# xbee_2017.net
KiCad netlist of a schematic drawn in EAGLE
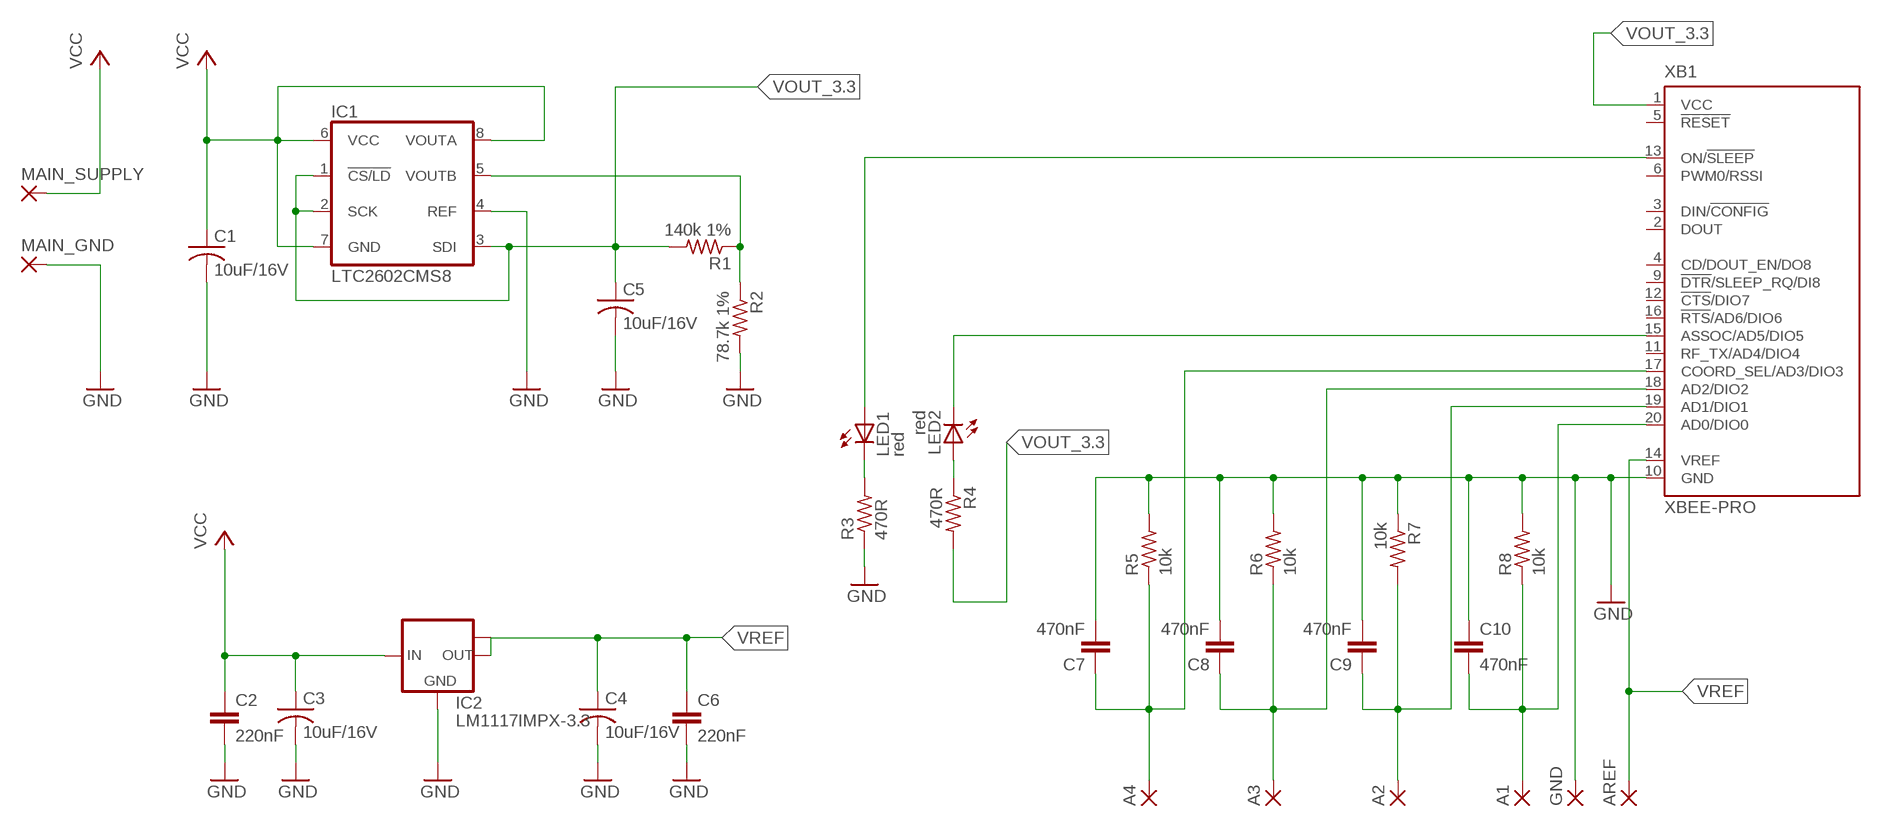
[diagram p0: schematic, sheet 1]

(export (version "E")
  (design (tool "Eeschema 10.0.6"))
  (components
    (comp (ref "A1")
      (value "2,54/0,9")
      (footprint "eagle-import:2,54_0,9")
      (libsource (lib "eagle-import") (part "2,54/0,9"))
    )
    (comp (ref "A2")
      (value "2,54/0,9")
      (footprint "eagle-import:2,54_0,9")
      (libsource (lib "eagle-import") (part "2,54/0,9"))
    )
    (comp (ref "A3")
      (value "2,54/0,9")
      (footprint "eagle-import:2,54_0,9")
      (libsource (lib "eagle-import") (part "2,54/0,9"))
    )
    (comp (ref "A4")
      (value "2,54/0,9")
      (footprint "eagle-import:2,54_0,9")
      (libsource (lib "eagle-import") (part "2,54/0,9"))
    )
    (comp (ref "AREF")
      (value "2,54/0,9")
      (footprint "eagle-import:2,54_0,9")
      (libsource (lib "eagle-import") (part "2,54/0,9"))
    )
    (comp (ref "C1")
      (value "10uF/16V")
      (footprint "eagle-import:C025-030X050")
      (libsource (lib "eagle-import") (part "C-US025-030X050"))
    )
    (comp (ref "C2")
      (value "220nF")
      (footprint "eagle-import:C025-025X050")
      (libsource (lib "eagle-import") (part "C-EU025-025X050"))
    )
    (comp (ref "C3")
      (value "10uF/16V")
      (footprint "eagle-import:C025-030X050")
      (libsource (lib "eagle-import") (part "C-US025-030X050"))
    )
    (comp (ref "C4")
      (value "10uF/16V")
      (footprint "eagle-import:C025-030X050")
      (libsource (lib "eagle-import") (part "C-US025-030X050"))
    )
    (comp (ref "C5")
      (value "10uF/16V")
      (footprint "eagle-import:C025-030X050")
      (libsource (lib "eagle-import") (part "C-US025-030X050"))
    )
    (comp (ref "C6")
      (value "220nF")
      (footprint "eagle-import:C025-025X050")
      (libsource (lib "eagle-import") (part "C-EU025-025X050"))
    )
    (comp (ref "C7")
      (value "470nF")
      (footprint "eagle-import:C5B2.5")
      (libsource (lib "eagle-import") (part "C5/2.5"))
    )
    (comp (ref "C8")
      (value "470nF")
      (footprint "eagle-import:C5B2.5")
      (libsource (lib "eagle-import") (part "C5/2.5"))
    )
    (comp (ref "C9")
      (value "470nF")
      (footprint "eagle-import:C5B2.5")
      (libsource (lib "eagle-import") (part "C5/2.5"))
    )
    (comp (ref "C10")
      (value "470nF")
      (footprint "eagle-import:C5B2.5")
      (libsource (lib "eagle-import") (part "C5/2.5"))
    )
    (comp (ref "GND")
      (value "2,54/0,9")
      (footprint "eagle-import:2,54_0,9")
      (libsource (lib "eagle-import") (part "2,54/0,9"))
    )
    (comp (ref "IC1")
      (value "LTC2602CMS8")
      (footprint "eagle-import:MSOP8")
      (libsource (lib "eagle-import") (part "LTC26MS802C"))
    )
    (comp (ref "IC2")
      (value "LM1117IMPX-3.3")
      (footprint "eagle-import:SOT223")
      (libsource (lib "eagle-import") (part "LM1117IMPX-3.3"))
    )
    (comp (ref "LED1")
      (value "red")
      (footprint "eagle-import:LED3MM")
      (libsource (lib "eagle-import") (part "LED3MM"))
    )
    (comp (ref "LED2")
      (value "red")
      (footprint "eagle-import:LED3MM")
      (libsource (lib "eagle-import") (part "LED3MM"))
    )
    (comp (ref "MAIN_GND")
      (value "3,17/1,3")
      (footprint "eagle-import:3,17_1,3")
      (libsource (lib "eagle-import") (part "3,17/1,3"))
    )
    (comp (ref "MAIN_SUPPLY")
      (value "3,17/1,3")
      (footprint "eagle-import:3,17_1,3")
      (libsource (lib "eagle-import") (part "3,17/1,3"))
    )
    (comp (ref "R1")
      (value "140k 1%")
      (footprint "eagle-import:0207_10")
      (libsource (lib "eagle-import") (part "R-US_0207/10"))
    )
    (comp (ref "R2")
      (value "78.7k 1%")
      (footprint "eagle-import:0207_10")
      (libsource (lib "eagle-import") (part "R-US_0207/10"))
    )
    (comp (ref "R3")
      (value "470R")
      (footprint "eagle-import:0207_10")
      (libsource (lib "eagle-import") (part "R-US_0207/10"))
    )
    (comp (ref "R4")
      (value "470R")
      (footprint "eagle-import:0207_10")
      (libsource (lib "eagle-import") (part "R-US_0207/10"))
    )
    (comp (ref "R5")
      (value "10k")
      (footprint "eagle-import:0207_10")
      (libsource (lib "eagle-import") (part "R-US_0207/10"))
    )
    (comp (ref "R6")
      (value "10k")
      (footprint "eagle-import:0207_10")
      (libsource (lib "eagle-import") (part "R-US_0207/10"))
    )
    (comp (ref "R7")
      (value "10k")
      (footprint "eagle-import:0207_10")
      (libsource (lib "eagle-import") (part "R-US_0207/10"))
    )
    (comp (ref "R8")
      (value "10k")
      (footprint "eagle-import:0207_10")
      (libsource (lib "eagle-import") (part "R-US_0207/10"))
    )
    (comp (ref "XB1")
      (value "XBEE-PRO")
      (footprint "eagle-import:XBEE-PRO")
      (fields (field (name "MPN") "XBP24-AWI-001"))
      (libsource (lib "eagle-import") (part "XBEE-PRO"))
    )
  )
  (nets
    (net (code "1") (name "GND") (class "Default")
      (node (ref "C1") (pin "2") (pinfunction "2_2") (pintype "passive"))
      (node (ref "C10") (pin "1") (pinfunction "1_1") (pintype "passive"))
      (node (ref "C2") (pin "2") (pinfunction "2_2") (pintype "passive"))
      (node (ref "C3") (pin "2") (pinfunction "2_2") (pintype "passive"))
      (node (ref "C4") (pin "2") (pinfunction "2_2") (pintype "passive"))
      (node (ref "C5") (pin "2") (pinfunction "2_2") (pintype "passive"))
      (node (ref "C6") (pin "2") (pinfunction "2_2") (pintype "passive"))
      (node (ref "C7") (pin "2") (pinfunction "2_2") (pintype "passive"))
      (node (ref "C8") (pin "2") (pinfunction "2_2") (pintype "passive"))
      (node (ref "C9") (pin "2") (pinfunction "2_2") (pintype "passive"))
      (node (ref "GND") (pin "1") (pinfunction "P_1") (pintype "passive"))
      (node (ref "IC1") (pin "4") (pinfunction "REF_4") (pintype "input"))
      (node (ref "IC2") (pin "1") (pinfunction "GND_1") (pintype "input"))
      (node (ref "MAIN_GND") (pin "1") (pinfunction "P_1") (pintype "passive"))
      (node (ref "R2") (pin "2") (pinfunction "2_2") (pintype "passive"))
      (node (ref "R3") (pin "1") (pinfunction "1_1") (pintype "passive"))
      (node (ref "R5") (pin "2") (pinfunction "2_2") (pintype "passive"))
      (node (ref "R6") (pin "2") (pinfunction "2_2") (pintype "passive"))
      (node (ref "R7") (pin "1") (pinfunction "1_1") (pintype "passive"))
      (node (ref "R8") (pin "2") (pinfunction "2_2") (pintype "passive"))
      (node (ref "XB1") (pin "10") (pinfunction "GND_10") (pintype "power_in"))
    )
    (net (code "2") (name "Net-(A1-P)") (class "Default")
      (node (ref "A1") (pin "1") (pinfunction "P_1") (pintype "passive"))
      (node (ref "C10") (pin "2") (pinfunction "2_2") (pintype "passive"))
      (node (ref "R8") (pin "1") (pinfunction "1_1") (pintype "passive"))
      (node (ref "XB1") (pin "20") (pinfunction "AD0/DIO0_20") (pintype "bidirectional"))
    )
    (net (code "3") (name "Net-(A2-P)") (class "Default")
      (node (ref "A2") (pin "1") (pinfunction "P_1") (pintype "passive"))
      (node (ref "C9") (pin "1") (pinfunction "1_1") (pintype "passive"))
      (node (ref "R7") (pin "2") (pinfunction "2_2") (pintype "passive"))
      (node (ref "XB1") (pin "19") (pinfunction "AD1/DIO1_19") (pintype "bidirectional"))
    )
    (net (code "4") (name "Net-(A3-P)") (class "Default")
      (node (ref "A3") (pin "1") (pinfunction "P_1") (pintype "passive"))
      (node (ref "C8") (pin "1") (pinfunction "1_1") (pintype "passive"))
      (node (ref "R6") (pin "1") (pinfunction "1_1") (pintype "passive"))
      (node (ref "XB1") (pin "18") (pinfunction "AD2/DIO2_18") (pintype "bidirectional"))
    )
    (net (code "5") (name "Net-(A4-P)") (class "Default")
      (node (ref "A4") (pin "1") (pinfunction "P_1") (pintype "passive"))
      (node (ref "C7") (pin "1") (pinfunction "1_1") (pintype "passive"))
      (node (ref "R5") (pin "1") (pinfunction "1_1") (pintype "passive"))
      (node (ref "XB1") (pin "17") (pinfunction "COORD_SEL/AD3/DIO3_17") (pintype "bidirectional"))
    )
    (net (code "6") (name "Net-(IC1-VOUTB)") (class "Default")
      (node (ref "IC1") (pin "5") (pinfunction "VOUTB_5") (pintype "output"))
      (node (ref "R1") (pin "1") (pinfunction "1_1") (pintype "passive"))
      (node (ref "R2") (pin "1") (pinfunction "1_1") (pintype "passive"))
    )
    (net (code "7") (name "Net-(LED1-C)") (class "Default")
      (node (ref "LED1") (pin "K") (pinfunction "C_K") (pintype "passive"))
      (node (ref "R3") (pin "2") (pinfunction "2_2") (pintype "passive"))
    )
    (net (code "8") (name "Net-(LED2-C)") (class "Default")
      (node (ref "LED2") (pin "K") (pinfunction "C_K") (pintype "passive"))
      (node (ref "XB1") (pin "15") (pinfunction "ASSOC/AD5/DIO5_15") (pintype "bidirectional"))
    )
    (net (code "9") (name "Net-(LED2-PadA)") (class "Default")
      (node (ref "LED2") (pin "A") (pinfunction "A_A") (pintype "passive"))
      (node (ref "R4") (pin "1") (pinfunction "1_1") (pintype "passive"))
    )
    (net (code "10") (name "Net-(XB1-ON{slash}~{SLEEP})") (class "Default")
      (node (ref "LED1") (pin "A") (pinfunction "A_A") (pintype "passive"))
      (node (ref "XB1") (pin "13") (pinfunction "ON/~{SLEEP}_13") (pintype "output"))
    )
    (net (code "11") (name "VCC") (class "Default")
      (node (ref "C1") (pin "1") (pinfunction "1_1") (pintype "passive"))
      (node (ref "C2") (pin "1") (pinfunction "1_1") (pintype "passive"))
      (node (ref "C3") (pin "1") (pinfunction "1_1") (pintype "passive"))
      (node (ref "IC1") (pin "6") (pinfunction "VCC_6") (pintype "power_in"))
      (node (ref "IC1") (pin "7") (pinfunction "GND_7") (pintype "power_in"))
      (node (ref "IC1") (pin "8") (pinfunction "VOUTA_8") (pintype "output"))
      (node (ref "IC2") (pin "3") (pinfunction "IN_3") (pintype "input"))
      (node (ref "MAIN_SUPPLY") (pin "1") (pinfunction "P_1") (pintype "passive"))
    )
    (net (code "12") (name "VOUT_3.3") (class "Default")
      (node (ref "C5") (pin "1") (pinfunction "1_1") (pintype "passive"))
      (node (ref "IC1") (pin "1") (pinfunction "~{CS/LD}_1") (pintype "input"))
      (node (ref "IC1") (pin "2") (pinfunction "SCK_2") (pintype "input"))
      (node (ref "IC1") (pin "3") (pinfunction "SDI_3") (pintype "input"))
      (node (ref "R1") (pin "2") (pinfunction "2_2") (pintype "passive"))
      (node (ref "R4") (pin "2") (pinfunction "2_2") (pintype "passive"))
      (node (ref "XB1") (pin "1") (pinfunction "VCC_1") (pintype "power_in"))
    )
    (net (code "13") (name "VREF") (class "Default")
      (node (ref "AREF") (pin "1") (pinfunction "P_1") (pintype "passive"))
      (node (ref "C4") (pin "1") (pinfunction "1_1") (pintype "passive"))
      (node (ref "C6") (pin "1") (pinfunction "1_1") (pintype "passive"))
      (node (ref "IC2") (pin "2") (pinfunction "OUT_2") (pintype "passive"))
      (node (ref "IC2") (pin "TAB") (pinfunction "OUT1_TAB") (pintype "passive"))
      (node (ref "XB1") (pin "14") (pinfunction "VREF_14") (pintype "input"))
    )
    (net (code "14") (name "unconnected-(XB1-CD{slash}DOUT_EN{slash}DO8-Pad4)") (class "Default")
      (node (ref "XB1") (pin "4") (pinfunction "CD/DOUT_EN/DO8_4") (pintype "output"))
    )
    (net (code "15") (name "unconnected-(XB1-DIN{slash}~{CONFIG}-Pad3)") (class "Default")
      (node (ref "XB1") (pin "3") (pinfunction "DIN/~{CONFIG}_3") (pintype "input"))
    )
    (net (code "16") (name "unconnected-(XB1-DOUT-Pad2)") (class "Default")
      (node (ref "XB1") (pin "2") (pinfunction "DOUT_2") (pintype "output"))
    )
    (net (code "17") (name "unconnected-(XB1-PWM0{slash}RSSI-Pad6)") (class "Default")
      (node (ref "XB1") (pin "6") (pinfunction "PWM0/RSSI_6") (pintype "output"))
    )
    (net (code "18") (name "unconnected-(XB1-RF_TX{slash}AD4{slash}DIO4-Pad11)") (class "Default")
      (node (ref "XB1") (pin "11") (pinfunction "RF_TX/AD4/DIO4_11") (pintype "bidirectional"))
    )
    (net (code "19") (name "unconnected-(XB1-~{CTS}{slash}DIO7-Pad12)") (class "Default")
      (node (ref "XB1") (pin "12") (pinfunction "~{CTS}/DIO7_12") (pintype "bidirectional"))
    )
    (net (code "20") (name "unconnected-(XB1-~{DTR}{slash}SLEEP_RQ{slash}DI8-Pad9)") (class "Default")
      (node (ref "XB1") (pin "9") (pinfunction "~{DTR}/SLEEP_RQ/DI8_9") (pintype "bidirectional"))
    )
    (net (code "21") (name "unconnected-(XB1-~{RESET}-Pad5)") (class "Default")
      (node (ref "XB1") (pin "5") (pinfunction "~{RESET}_5") (pintype "input"))
    )
    (net (code "22") (name "unconnected-(XB1-~{RTS}{slash}AD6{slash}DIO6-Pad16)") (class "Default")
      (node (ref "XB1") (pin "16") (pinfunction "~{RTS}/AD6/DIO6_16") (pintype "bidirectional"))
    )
  )
)
